# receiving_end_2.net
KiCad netlist of a schematic drawn in EAGLE
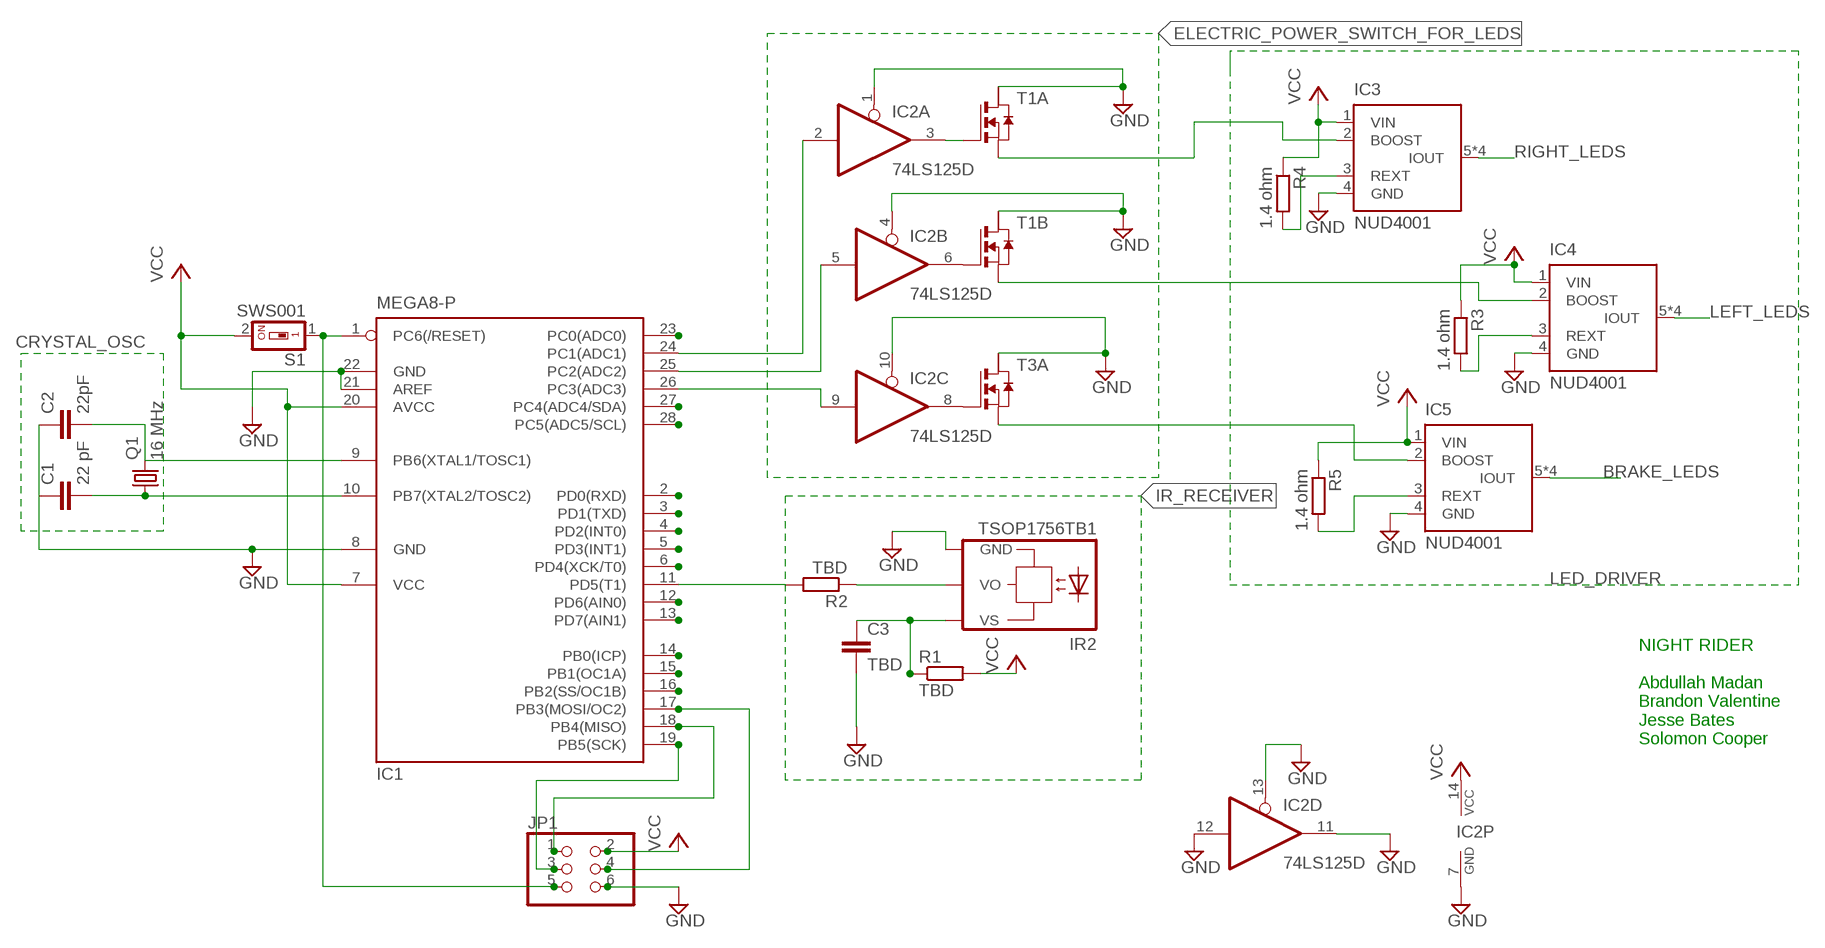
[diagram p0: schematic, sheet 1]

(export (version "E")
  (design (tool "Eeschema 10.0.6"))
  (components
    (comp (ref "C1")
      (value "22 pF")
      (footprint "eagle-import:C1206")
      (libsource (lib "eagle-import") (part "C-EUC1206"))
    )
    (comp (ref "C2")
      (value "22pF")
      (footprint "eagle-import:C1206")
      (libsource (lib "eagle-import") (part "C-EUC1206"))
    )
    (comp (ref "C3")
      (value "TBD")
      (footprint "eagle-import:C0805")
      (libsource (lib "eagle-import") (part "C-EUC0805"))
    )
    (comp (ref "IC1")
      (value "MEGA8-P")
      (footprint "eagle-import:DIL28-3")
      (libsource (lib "eagle-import") (part "MEGA8-P"))
    )
    (comp (ref "IC2")
      (value "74LS125D")
      (footprint "eagle-import:SO14")
      (libsource (lib "eagle-import") (part "74125DLS"))
    )
    (comp (ref "IC3")
      (value "NUD4001")
      (footprint "eagle-import:SO-8")
      (libsource (lib "eagle-import") (part "NUD4001"))
    )
    (comp (ref "IC4")
      (value "NUD4001")
      (footprint "eagle-import:SO-8")
      (libsource (lib "eagle-import") (part "NUD4001"))
    )
    (comp (ref "IC5")
      (value "NUD4001")
      (footprint "eagle-import:SO-8")
      (libsource (lib "eagle-import") (part "NUD4001"))
    )
    (comp (ref "IR2")
      (value "TSOP1756TB1")
      (footprint "eagle-import:TSOP17_TB1")
      (libsource (lib "eagle-import") (part "TSOP17TB156"))
    )
    (comp (ref "JP1")
      (value "PINHD-2X3")
      (footprint "eagle-import:2X03")
      (libsource (lib "eagle-import") (part "PINHD-2X3"))
    )
    (comp (ref "Q1")
      (value "16 MHz")
      (footprint "eagle-import:MC-405")
      (libsource (lib "eagle-import") (part "MC-405"))
    )
    (comp (ref "R1")
      (value "TBD")
      (footprint "eagle-import:R0805")
      (libsource (lib "eagle-import") (part "R-EU_R0805"))
    )
    (comp (ref "R2")
      (value "TBD")
      (footprint "eagle-import:R0805")
      (libsource (lib "eagle-import") (part "R-EU_R0805"))
    )
    (comp (ref "R3")
      (value "1.4 ohm")
      (footprint "eagle-import:R0805")
      (libsource (lib "eagle-import") (part "R-EU_R0805"))
    )
    (comp (ref "R4")
      (value "1.4 ohm")
      (footprint "eagle-import:R0805")
      (libsource (lib "eagle-import") (part "R-EU_R0805"))
    )
    (comp (ref "R5")
      (value "1.4 ohm")
      (footprint "eagle-import:R0805")
      (libsource (lib "eagle-import") (part "R-EU_R0805"))
    )
    (comp (ref "S1")
      (value "SWS001")
      (footprint "eagle-import:SMS-001")
      (libsource (lib "eagle-import") (part "SWS001"))
    )
    (comp (ref "T1")
      (value "NMOS2SM8")
      (footprint "eagle-import:SM8")
      (libsource (lib "eagle-import") (part "NMOS2SM8"))
    )
    (comp (ref "T3")
      (value "NMOS2SM8")
      (footprint "eagle-import:SM8")
      (libsource (lib "eagle-import") (part "NMOS2SM8"))
    )
  )
  (nets
    (net (code "1") (name "/BRAKE_LEDS") (class "Default")
      (node (ref "IC5") (pin "5") (pinfunction "IOUT_5") (pintype "passive"))
      (node (ref "IC5") (pin "6") (pinfunction "IOUT_6") (pintype "passive"))
      (node (ref "IC5") (pin "7") (pinfunction "IOUT_7") (pintype "passive"))
      (node (ref "IC5") (pin "8") (pinfunction "IOUT_8") (pintype "passive"))
    )
    (net (code "4") (name "/LEFT_LEDS") (class "Default")
      (node (ref "IC4") (pin "5") (pinfunction "IOUT_5") (pintype "passive"))
      (node (ref "IC4") (pin "6") (pinfunction "IOUT_6") (pintype "passive"))
      (node (ref "IC4") (pin "7") (pinfunction "IOUT_7") (pintype "passive"))
      (node (ref "IC4") (pin "8") (pinfunction "IOUT_8") (pintype "passive"))
    )
    (net (code "5") (name "/RIGHT_LEDS") (class "Default")
      (node (ref "IC3") (pin "5") (pinfunction "IOUT_5") (pintype "passive"))
      (node (ref "IC3") (pin "6") (pinfunction "IOUT_6") (pintype "passive"))
      (node (ref "IC3") (pin "7") (pinfunction "IOUT_7") (pintype "passive"))
      (node (ref "IC3") (pin "8") (pinfunction "IOUT_8") (pintype "passive"))
    )
    (net (code "7") (name "GND") (class "Default")
      (node (ref "C1") (pin "1") (pinfunction "1_1") (pintype "passive"))
      (node (ref "C2") (pin "1") (pinfunction "1_1") (pintype "passive"))
      (node (ref "C3") (pin "2") (pinfunction "2_2") (pintype "passive"))
      (node (ref "IC1") (pin "21") (pinfunction "AREF_21") (pintype "passive"))
      (node (ref "IC1") (pin "22") (pinfunction "GND_22") (pintype "power_in"))
      (node (ref "IC1") (pin "8") (pinfunction "GND_8") (pintype "power_in"))
      (node (ref "IC2") (pin "1") (pinfunction "OE_1") (pintype "input"))
      (node (ref "IC2") (pin "10") (pinfunction "OE_10") (pintype "input"))
      (node (ref "IC2") (pin "11") (pinfunction "O_11") (pintype "tri_state"))
      (node (ref "IC2") (pin "12") (pinfunction "I_12") (pintype "input"))
      (node (ref "IC2") (pin "13") (pinfunction "OE_13") (pintype "input"))
      (node (ref "IC2") (pin "4") (pinfunction "OE_4") (pintype "input"))
      (node (ref "IC2") (pin "7") (pinfunction "GND_7") (pintype "power_in"))
      (node (ref "IC3") (pin "4") (pinfunction "GND_4") (pintype "power_in"))
      (node (ref "IC4") (pin "4") (pinfunction "GND_4") (pintype "power_in"))
      (node (ref "IC5") (pin "4") (pinfunction "GND_4") (pintype "power_in"))
      (node (ref "IR2") (pin "GND") (pinfunction "GND_GND") (pintype "power_in"))
      (node (ref "JP1") (pin "6") (pinfunction "6_6") (pintype "passive"))
      (node (ref "T1") (pin "5") (pinfunction "D_5") (pintype "passive"))
      (node (ref "T1") (pin "7") (pinfunction "D_7") (pintype "passive"))
      (node (ref "T3") (pin "5") (pinfunction "D_5") (pintype "passive"))
    )
    (net (code "9") (name "Net-(C3-Pad1)") (class "Default")
      (node (ref "C3") (pin "1") (pinfunction "1_1") (pintype "passive"))
      (node (ref "IR2") (pin "VS") (pinfunction "VS_VS") (pintype "power_in"))
      (node (ref "R1") (pin "1") (pinfunction "1_1") (pintype "passive"))
    )
    (net (code "10") (name "Net-(IC1-PB3(MOSI{slash}OC2))") (class "Default")
      (node (ref "IC1") (pin "17") (pinfunction "PB3(MOSI/OC2)_17") (pintype "bidirectional"))
      (node (ref "JP1") (pin "4") (pinfunction "4_4") (pintype "passive"))
    )
    (net (code "11") (name "Net-(IC1-PB4(MISO))") (class "Default")
      (node (ref "IC1") (pin "18") (pinfunction "PB4(MISO)_18") (pintype "bidirectional"))
      (node (ref "JP1") (pin "1") (pinfunction "1_1") (pintype "passive"))
    )
    (net (code "12") (name "Net-(IC1-PB5(SCK))") (class "Default")
      (node (ref "IC1") (pin "19") (pinfunction "PB5(SCK)_19") (pintype "bidirectional"))
      (node (ref "JP1") (pin "3") (pinfunction "3_3") (pintype "passive"))
    )
    (net (code "13") (name "Net-(IC1-PB6(XTAL1{slash}TOSC1))") (class "Default")
      (node (ref "C2") (pin "2") (pinfunction "2_2") (pintype "passive"))
      (node (ref "IC1") (pin "9") (pinfunction "PB6(XTAL1/TOSC1)_9") (pintype "bidirectional"))
      (node (ref "Q1") (pin "2") (pinfunction "2_2") (pintype "passive"))
    )
    (net (code "14") (name "Net-(IC1-PB7(XTAL2{slash}TOSC2))") (class "Default")
      (node (ref "C1") (pin "2") (pinfunction "2_2") (pintype "passive"))
      (node (ref "IC1") (pin "10") (pinfunction "PB7(XTAL2/TOSC2)_10") (pintype "bidirectional"))
      (node (ref "Q1") (pin "1") (pinfunction "1_1") (pintype "passive"))
    )
    (net (code "15") (name "Net-(IC1-PC1(ADC1))") (class "Default")
      (node (ref "IC1") (pin "24") (pinfunction "PC1(ADC1)_24") (pintype "bidirectional"))
      (node (ref "IC2") (pin "2") (pinfunction "I_2") (pintype "input"))
    )
    (net (code "16") (name "Net-(IC1-PC2(ADC2))") (class "Default")
      (node (ref "IC1") (pin "25") (pinfunction "PC2(ADC2)_25") (pintype "bidirectional"))
      (node (ref "IC2") (pin "5") (pinfunction "I_5") (pintype "input"))
    )
    (net (code "17") (name "Net-(IC1-PC3(ADC3))") (class "Default")
      (node (ref "IC1") (pin "26") (pinfunction "PC3(ADC3)_26") (pintype "bidirectional"))
      (node (ref "IC2") (pin "9") (pinfunction "I_9") (pintype "input"))
    )
    (net (code "18") (name "Net-(IC1-PC6({slash}RESET))") (class "Default")
      (node (ref "IC1") (pin "1") (pinfunction "PC6(/RESET)_1") (pintype "bidirectional"))
      (node (ref "JP1") (pin "5") (pinfunction "5_5") (pintype "passive"))
      (node (ref "S1") (pin "1") (pinfunction "1_1") (pintype "passive"))
    )
    (net (code "19") (name "Net-(IC1-PD5(T1))") (class "Default")
      (node (ref "IC1") (pin "11") (pinfunction "PD5(T1)_11") (pintype "bidirectional"))
      (node (ref "R2") (pin "2") (pinfunction "2_2") (pintype "passive"))
    )
    (net (code "20") (name "Net-(IC2A-O)") (class "Default")
      (node (ref "IC2") (pin "3") (pinfunction "O_3") (pintype "tri_state"))
      (node (ref "T1") (pin "4") (pinfunction "G_4") (pintype "passive"))
    )
    (net (code "21") (name "Net-(IC2B-O)") (class "Default")
      (node (ref "IC2") (pin "6") (pinfunction "O_6") (pintype "tri_state"))
      (node (ref "T1") (pin "2") (pinfunction "G_2") (pintype "passive"))
    )
    (net (code "22") (name "Net-(IC2C-O)") (class "Default")
      (node (ref "IC2") (pin "8") (pinfunction "O_8") (pintype "tri_state"))
      (node (ref "T3") (pin "4") (pinfunction "G_4") (pintype "passive"))
    )
    (net (code "23") (name "Net-(IC3-BOOST)") (class "Default")
      (node (ref "IC3") (pin "2") (pinfunction "BOOST_2") (pintype "passive"))
      (node (ref "T1") (pin "3") (pinfunction "S_3") (pintype "passive"))
    )
    (net (code "24") (name "Net-(IC3-REXT)") (class "Default")
      (node (ref "IC3") (pin "3") (pinfunction "REXT_3") (pintype "passive"))
      (node (ref "R4") (pin "2") (pinfunction "2_2") (pintype "passive"))
    )
    (net (code "25") (name "Net-(IC4-BOOST)") (class "Default")
      (node (ref "IC4") (pin "2") (pinfunction "BOOST_2") (pintype "passive"))
      (node (ref "T1") (pin "1") (pinfunction "S_1") (pintype "passive"))
    )
    (net (code "26") (name "Net-(IC4-REXT)") (class "Default")
      (node (ref "IC4") (pin "3") (pinfunction "REXT_3") (pintype "passive"))
      (node (ref "R3") (pin "2") (pinfunction "2_2") (pintype "passive"))
    )
    (net (code "27") (name "Net-(IC5-BOOST)") (class "Default")
      (node (ref "IC5") (pin "2") (pinfunction "BOOST_2") (pintype "passive"))
      (node (ref "T3") (pin "3") (pinfunction "S_3") (pintype "passive"))
    )
    (net (code "28") (name "Net-(IC5-REXT)") (class "Default")
      (node (ref "IC5") (pin "3") (pinfunction "REXT_3") (pintype "passive"))
      (node (ref "R5") (pin "2") (pinfunction "2_2") (pintype "passive"))
    )
    (net (code "29") (name "Net-(IR2-PadVO)") (class "Default")
      (node (ref "IR2") (pin "VO") (pinfunction "VO_VO") (pintype "open_collector"))
      (node (ref "R2") (pin "1") (pinfunction "1_1") (pintype "passive"))
    )
    (net (code "30") (name "VCC") (class "Default")
      (node (ref "IC1") (pin "20") (pinfunction "AVCC_20") (pintype "power_in"))
      (node (ref "IC1") (pin "7") (pinfunction "VCC_7") (pintype "power_in"))
      (node (ref "IC2") (pin "14") (pinfunction "VCC_14") (pintype "power_in"))
      (node (ref "IC3") (pin "1") (pinfunction "VIN_1") (pintype "input"))
      (node (ref "IC4") (pin "1") (pinfunction "VIN_1") (pintype "input"))
      (node (ref "IC5") (pin "1") (pinfunction "VIN_1") (pintype "input"))
      (node (ref "JP1") (pin "2") (pinfunction "2_2") (pintype "passive"))
      (node (ref "R1") (pin "2") (pinfunction "2_2") (pintype "passive"))
      (node (ref "R3") (pin "1") (pinfunction "1_1") (pintype "passive"))
      (node (ref "R4") (pin "1") (pinfunction "1_1") (pintype "passive"))
      (node (ref "R5") (pin "1") (pinfunction "1_1") (pintype "passive"))
      (node (ref "S1") (pin "2") (pinfunction "2_2") (pintype "passive"))
    )
    (net (code "31") (name "unconnected-(IC1-PB0(ICP)-Pad14)") (class "Default")
      (node (ref "IC1") (pin "14") (pinfunction "PB0(ICP)_14") (pintype "bidirectional"))
    )
    (net (code "32") (name "unconnected-(IC1-PB1(OC1A)-Pad15)") (class "Default")
      (node (ref "IC1") (pin "15") (pinfunction "PB1(OC1A)_15") (pintype "bidirectional"))
    )
    (net (code "33") (name "unconnected-(IC1-PB2(SS{slash}OC1B)-Pad16)") (class "Default")
      (node (ref "IC1") (pin "16") (pinfunction "PB2(SS/OC1B)_16") (pintype "bidirectional"))
    )
    (net (code "34") (name "unconnected-(IC1-PC0(ADC0)-Pad23)") (class "Default")
      (node (ref "IC1") (pin "23") (pinfunction "PC0(ADC0)_23") (pintype "bidirectional"))
    )
    (net (code "35") (name "unconnected-(IC1-PC4(ADC4{slash}SDA)-Pad27)") (class "Default")
      (node (ref "IC1") (pin "27") (pinfunction "PC4(ADC4/SDA)_27") (pintype "bidirectional"))
    )
    (net (code "36") (name "unconnected-(IC1-PC5(ADC5{slash}SCL)-Pad28)") (class "Default")
      (node (ref "IC1") (pin "28") (pinfunction "PC5(ADC5/SCL)_28") (pintype "bidirectional"))
    )
    (net (code "37") (name "unconnected-(IC1-PD0(RXD)-Pad2)") (class "Default")
      (node (ref "IC1") (pin "2") (pinfunction "PD0(RXD)_2") (pintype "bidirectional"))
    )
    (net (code "38") (name "unconnected-(IC1-PD1(TXD)-Pad3)") (class "Default")
      (node (ref "IC1") (pin "3") (pinfunction "PD1(TXD)_3") (pintype "bidirectional"))
    )
    (net (code "39") (name "unconnected-(IC1-PD2(INT0)-Pad4)") (class "Default")
      (node (ref "IC1") (pin "4") (pinfunction "PD2(INT0)_4") (pintype "bidirectional"))
    )
    (net (code "40") (name "unconnected-(IC1-PD3(INT1)-Pad5)") (class "Default")
      (node (ref "IC1") (pin "5") (pinfunction "PD3(INT1)_5") (pintype "bidirectional"))
    )
    (net (code "41") (name "unconnected-(IC1-PD4(XCK{slash}T0)-Pad6)") (class "Default")
      (node (ref "IC1") (pin "6") (pinfunction "PD4(XCK/T0)_6") (pintype "bidirectional"))
    )
    (net (code "42") (name "unconnected-(IC1-PD6(AIN0)-Pad12)") (class "Default")
      (node (ref "IC1") (pin "12") (pinfunction "PD6(AIN0)_12") (pintype "bidirectional"))
    )
    (net (code "43") (name "unconnected-(IC1-PD7(AIN1)-Pad13)") (class "Default")
      (node (ref "IC1") (pin "13") (pinfunction "PD7(AIN1)_13") (pintype "bidirectional"))
    )
    (net (code "44") (name "unconnected-(T1A-D2-Pad6)") (class "Default")
      (node (ref "T1") (pin "6") (pinfunction "D2_6") (pintype "passive"))
    )
    (net (code "45") (name "unconnected-(T1B-D2-Pad8)") (class "Default")
      (node (ref "T1") (pin "8") (pinfunction "D2_8") (pintype "passive"))
    )
    (net (code "46") (name "unconnected-(T3A-D2-Pad6)") (class "Default")
      (node (ref "T3") (pin "6") (pinfunction "D2_6") (pintype "passive"))
    )
  )
)
